# W511A.net
KiCad netlist of a schematic drawn in EAGLE
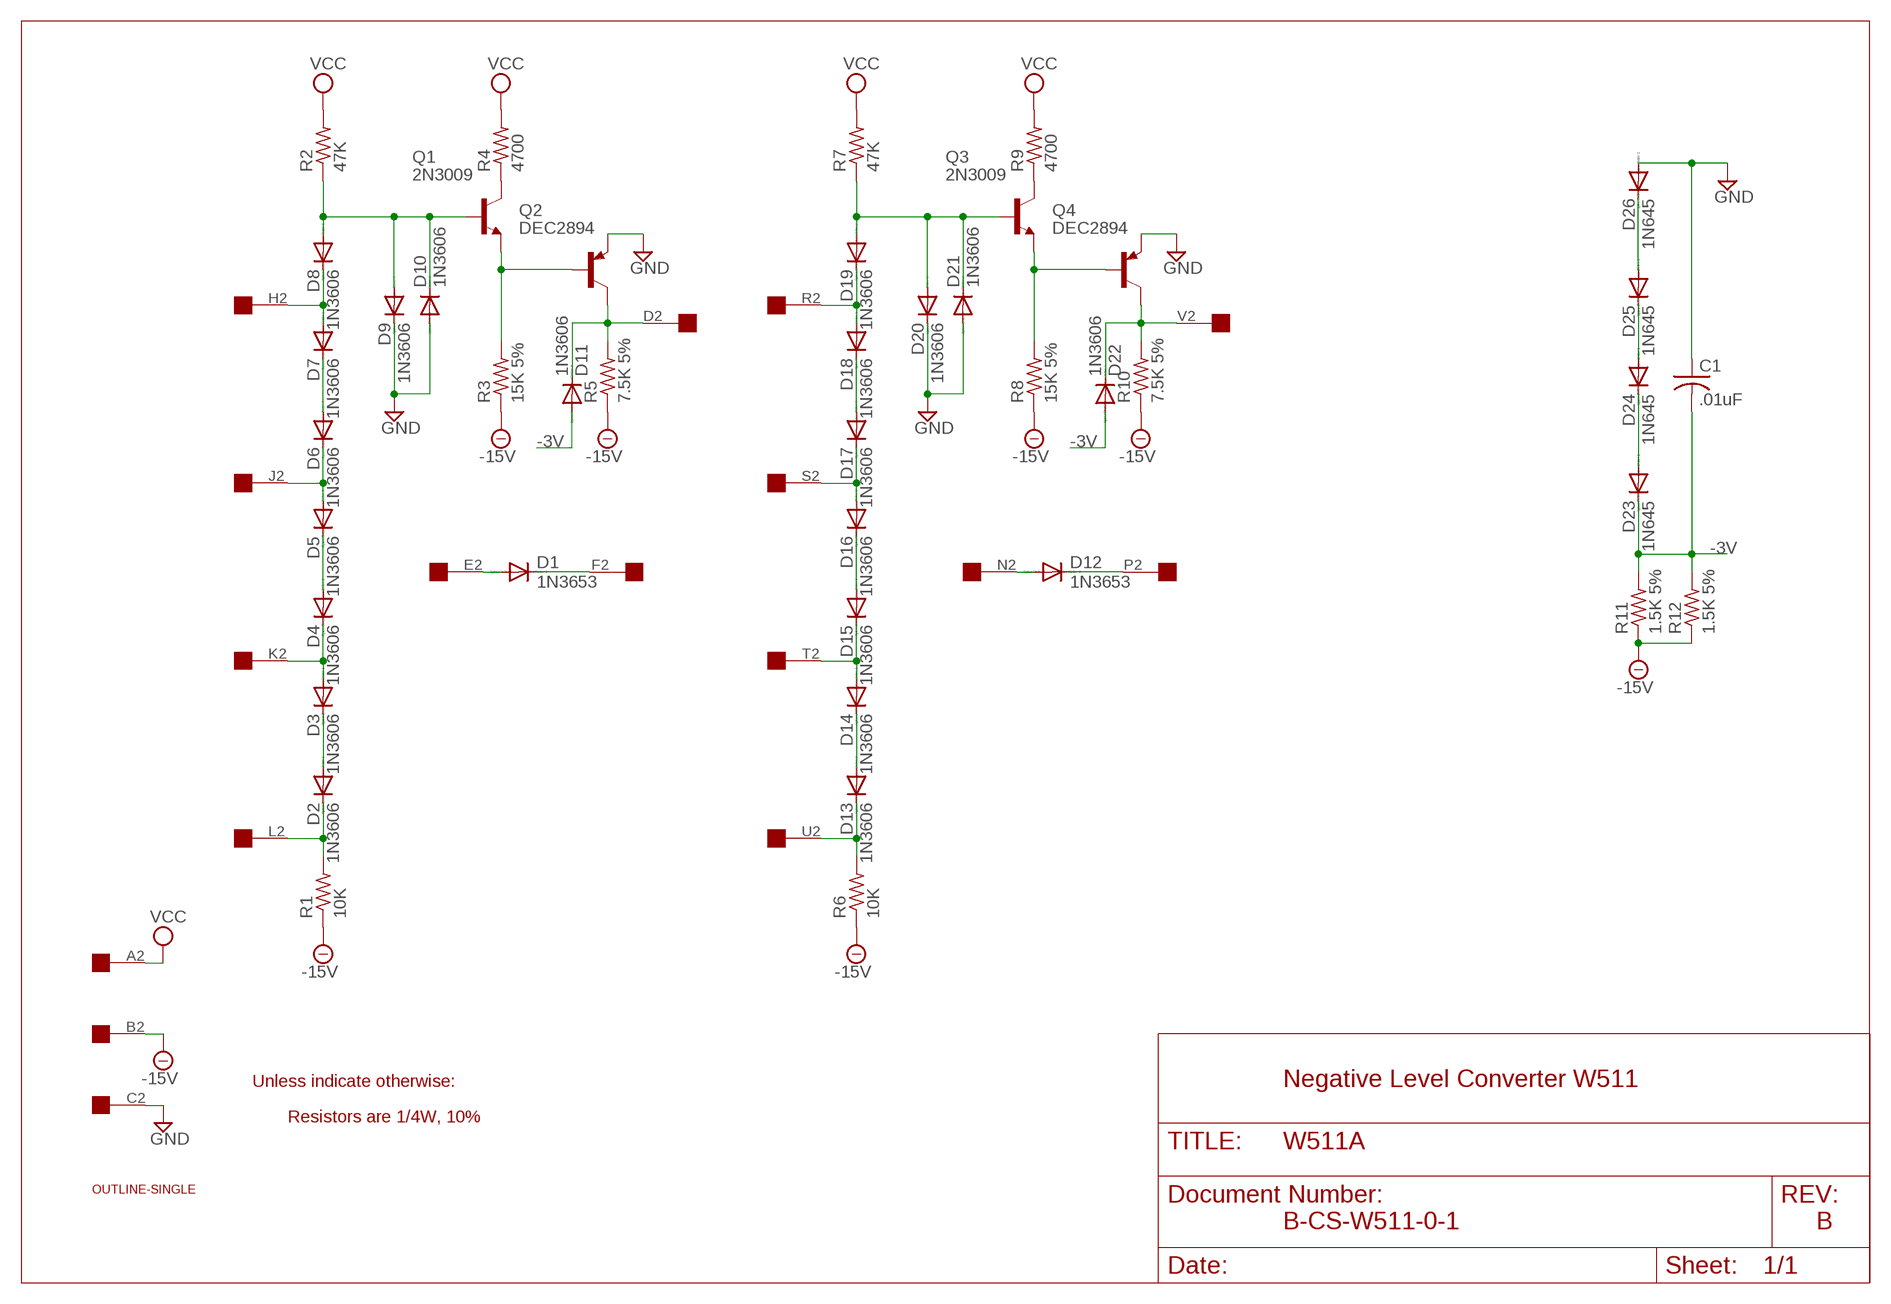
[diagram p0: schematic, sheet 1]

(export (version "E")
  (design (tool "Eeschema 10.0.6"))
  (components
    (comp (ref "C1")
      (value ".01uF")
      (footprint "eagle-import:C050-025X075")
      (libsource (lib "eagle-import") (part "C-US050-025X075"))
    )
    (comp (ref "D1")
      (value "1N3653")
      (footprint "eagle-import:DO35-10")
      (libsource (lib "eagle-import") (part "1N4148DO35-10"))
    )
    (comp (ref "D2")
      (value "1N3606")
      (footprint "eagle-import:DO35-10")
      (libsource (lib "eagle-import") (part "1N4148DO35-10"))
    )
    (comp (ref "D3")
      (value "1N3606")
      (footprint "eagle-import:DO35-10")
      (libsource (lib "eagle-import") (part "1N4148DO35-10"))
    )
    (comp (ref "D4")
      (value "1N3606")
      (footprint "eagle-import:DO35-10")
      (libsource (lib "eagle-import") (part "1N4148DO35-10"))
    )
    (comp (ref "D5")
      (value "1N3606")
      (footprint "eagle-import:DO35-10")
      (libsource (lib "eagle-import") (part "1N4148DO35-10"))
    )
    (comp (ref "D6")
      (value "1N3606")
      (footprint "eagle-import:DO35-10")
      (libsource (lib "eagle-import") (part "1N4148DO35-10"))
    )
    (comp (ref "D7")
      (value "1N3606")
      (footprint "eagle-import:DO35-10")
      (libsource (lib "eagle-import") (part "1N4148DO35-10"))
    )
    (comp (ref "D8")
      (value "1N3606")
      (footprint "eagle-import:DO35-10")
      (libsource (lib "eagle-import") (part "1N4148DO35-10"))
    )
    (comp (ref "D9")
      (value "1N3606")
      (footprint "eagle-import:DO35-10")
      (libsource (lib "eagle-import") (part "1N4148DO35-10"))
    )
    (comp (ref "D10")
      (value "1N3606")
      (footprint "eagle-import:DO35-10")
      (libsource (lib "eagle-import") (part "1N4148DO35-10"))
    )
    (comp (ref "D11")
      (value "1N3606")
      (footprint "eagle-import:DO35-10")
      (libsource (lib "eagle-import") (part "1N4148DO35-10"))
    )
    (comp (ref "D12")
      (value "1N3653")
      (footprint "eagle-import:DO35-10")
      (libsource (lib "eagle-import") (part "1N4148DO35-10"))
    )
    (comp (ref "D13")
      (value "1N3606")
      (footprint "eagle-import:DO35-10")
      (libsource (lib "eagle-import") (part "1N4148DO35-10"))
    )
    (comp (ref "D14")
      (value "1N3606")
      (footprint "eagle-import:DO35-10")
      (libsource (lib "eagle-import") (part "1N4148DO35-10"))
    )
    (comp (ref "D15")
      (value "1N3606")
      (footprint "eagle-import:DO35-10")
      (libsource (lib "eagle-import") (part "1N4148DO35-10"))
    )
    (comp (ref "D16")
      (value "1N3606")
      (footprint "eagle-import:DO35-10")
      (libsource (lib "eagle-import") (part "1N4148DO35-10"))
    )
    (comp (ref "D17")
      (value "1N3606")
      (footprint "eagle-import:DO35-10")
      (libsource (lib "eagle-import") (part "1N4148DO35-10"))
    )
    (comp (ref "D18")
      (value "1N3606")
      (footprint "eagle-import:DO35-10")
      (libsource (lib "eagle-import") (part "1N4148DO35-10"))
    )
    (comp (ref "D19")
      (value "1N3606")
      (footprint "eagle-import:DO35-10")
      (libsource (lib "eagle-import") (part "1N4148DO35-10"))
    )
    (comp (ref "D20")
      (value "1N3606")
      (footprint "eagle-import:DO35-10")
      (libsource (lib "eagle-import") (part "1N4148DO35-10"))
    )
    (comp (ref "D21")
      (value "1N3606")
      (footprint "eagle-import:DO35-10")
      (libsource (lib "eagle-import") (part "1N4148DO35-10"))
    )
    (comp (ref "D22")
      (value "1N3606")
      (footprint "eagle-import:DO35-10")
      (libsource (lib "eagle-import") (part "1N4148DO35-10"))
    )
    (comp (ref "D23")
      (value "1N645")
      (footprint "eagle-import:DO35-10")
      (libsource (lib "eagle-import") (part "1N4148DO35-10"))
    )
    (comp (ref "D24")
      (value "1N645")
      (footprint "eagle-import:DO35-10")
      (libsource (lib "eagle-import") (part "1N4148DO35-10"))
    )
    (comp (ref "D25")
      (value "1N645")
      (footprint "eagle-import:DO35-10")
      (libsource (lib "eagle-import") (part "1N4148DO35-10"))
    )
    (comp (ref "D26")
      (value "1N645")
      (footprint "eagle-import:DO35-10")
      (libsource (lib "eagle-import") (part "1N4148DO35-10"))
    )
    (comp (ref "EDGE")
      (value "EDGE-1")
      (footprint "eagle-import:EDGE-CON1")
      (libsource (lib "eagle-import") (part "EDGE-1"))
    )
    (comp (ref "Q1")
      (value "2N3009")
      (footprint "eagle-import:TO5")
      (libsource (lib "eagle-import") (part "2N2102"))
    )
    (comp (ref "Q2")
      (value "DEC2894")
      (footprint "eagle-import:TO39")
      (libsource (lib "eagle-import") (part "2N2904"))
    )
    (comp (ref "Q3")
      (value "2N3009")
      (footprint "eagle-import:TO5")
      (libsource (lib "eagle-import") (part "2N2102"))
    )
    (comp (ref "Q4")
      (value "DEC2894")
      (footprint "eagle-import:TO39")
      (libsource (lib "eagle-import") (part "2N2904"))
    )
    (comp (ref "R1")
      (value "10K")
      (footprint "eagle-import:0207_10")
      (libsource (lib "eagle-import") (part "R-US_0207/10"))
    )
    (comp (ref "R2")
      (value "47K")
      (footprint "eagle-import:0207_10")
      (libsource (lib "eagle-import") (part "R-US_0207/10"))
    )
    (comp (ref "R3")
      (value "15K 5%")
      (footprint "eagle-import:0207_10")
      (libsource (lib "eagle-import") (part "R-US_0207/10"))
    )
    (comp (ref "R4")
      (value "4700")
      (footprint "eagle-import:0207_10")
      (libsource (lib "eagle-import") (part "R-US_0207/10"))
    )
    (comp (ref "R5")
      (value "7.5K 5%")
      (footprint "eagle-import:0207_10")
      (libsource (lib "eagle-import") (part "R-US_0207/10"))
    )
    (comp (ref "R6")
      (value "10K")
      (footprint "eagle-import:0207_10")
      (libsource (lib "eagle-import") (part "R-US_0207/10"))
    )
    (comp (ref "R7")
      (value "47K")
      (footprint "eagle-import:0207_10")
      (libsource (lib "eagle-import") (part "R-US_0207/10"))
    )
    (comp (ref "R8")
      (value "15K 5%")
      (footprint "eagle-import:0207_10")
      (libsource (lib "eagle-import") (part "R-US_0207/10"))
    )
    (comp (ref "R9")
      (value "4700")
      (footprint "eagle-import:0207_10")
      (libsource (lib "eagle-import") (part "R-US_0207/10"))
    )
    (comp (ref "R10")
      (value "7.5K 5%")
      (footprint "eagle-import:0207_10")
      (libsource (lib "eagle-import") (part "R-US_0207/10"))
    )
    (comp (ref "R11")
      (value "1.5K 5%")
      (footprint "eagle-import:0207_10")
      (libsource (lib "eagle-import") (part "R-US_0207/10"))
    )
    (comp (ref "R12")
      (value "1.5K 5%")
      (footprint "eagle-import:0207_10")
      (libsource (lib "eagle-import") (part "R-US_0207/10"))
    )
    (comp (ref "U$1")
      (value "OUTLINE-SINGLE")
      (footprint "eagle-import:SINGLE")
      (libsource (lib "eagle-import") (part "OUTLINE-SINGLE"))
    )
  )
  (nets
    (net (code "1") (name "-15V") (class "Default")
      (node (ref "EDGE") (pin "B2") (pinfunction "1_B2") (pintype "bidirectional"))
      (node (ref "R1") (pin "1") (pinfunction "1_1") (pintype "passive"))
      (node (ref "R10") (pin "1") (pinfunction "1_1") (pintype "passive"))
      (node (ref "R11") (pin "1") (pinfunction "1_1") (pintype "passive"))
      (node (ref "R12") (pin "1") (pinfunction "1_1") (pintype "passive"))
      (node (ref "R3") (pin "1") (pinfunction "1_1") (pintype "passive"))
      (node (ref "R5") (pin "1") (pinfunction "1_1") (pintype "passive"))
      (node (ref "R6") (pin "1") (pinfunction "1_1") (pintype "passive"))
      (node (ref "R8") (pin "1") (pinfunction "1_1") (pintype "passive"))
    )
    (net (code "2") (name "/-3V") (class "Default")
      (node (ref "C1") (pin "2") (pinfunction "2_2") (pintype "passive"))
      (node (ref "D11") (pin "A") (pinfunction "A_A") (pintype "passive"))
      (node (ref "D22") (pin "A") (pinfunction "A_A") (pintype "passive"))
      (node (ref "D23") (pin "C") (pinfunction "C_C") (pintype "passive"))
      (node (ref "R11") (pin "2") (pinfunction "2_2") (pintype "passive"))
      (node (ref "R12") (pin "2") (pinfunction "2_2") (pintype "passive"))
    )
    (net (code "3") (name "GND") (class "Default")
      (node (ref "C1") (pin "1") (pinfunction "1_1") (pintype "passive"))
      (node (ref "D10") (pin "A") (pinfunction "A_A") (pintype "passive"))
      (node (ref "D20") (pin "C") (pinfunction "C_C") (pintype "passive"))
      (node (ref "D21") (pin "A") (pinfunction "A_A") (pintype "passive"))
      (node (ref "D26") (pin "A") (pinfunction "A_A") (pintype "passive"))
      (node (ref "D9") (pin "C") (pinfunction "C_C") (pintype "passive"))
      (node (ref "EDGE") (pin "C2") (pinfunction "1_C2") (pintype "bidirectional"))
      (node (ref "Q2") (pin "1") (pinfunction "E_1") (pintype "passive"))
      (node (ref "Q4") (pin "1") (pinfunction "E_1") (pintype "passive"))
    )
    (net (code "4") (name "Net-(D2-PadA)") (class "Default")
      (node (ref "D2") (pin "A") (pinfunction "A_A") (pintype "passive"))
      (node (ref "D3") (pin "C") (pinfunction "C_C") (pintype "passive"))
    )
    (net (code "5") (name "Net-(D4-PadA)") (class "Default")
      (node (ref "D4") (pin "A") (pinfunction "A_A") (pintype "passive"))
      (node (ref "D5") (pin "C") (pinfunction "C_C") (pintype "passive"))
    )
    (net (code "6") (name "Net-(D6-PadA)") (class "Default")
      (node (ref "D6") (pin "A") (pinfunction "A_A") (pintype "passive"))
      (node (ref "D7") (pin "C") (pinfunction "C_C") (pintype "passive"))
    )
    (net (code "7") (name "Net-(D13-PadA)") (class "Default")
      (node (ref "D13") (pin "A") (pinfunction "A_A") (pintype "passive"))
      (node (ref "D14") (pin "C") (pinfunction "C_C") (pintype "passive"))
    )
    (net (code "8") (name "Net-(D15-PadA)") (class "Default")
      (node (ref "D15") (pin "A") (pinfunction "A_A") (pintype "passive"))
      (node (ref "D16") (pin "C") (pinfunction "C_C") (pintype "passive"))
    )
    (net (code "9") (name "Net-(D17-PadA)") (class "Default")
      (node (ref "D17") (pin "A") (pinfunction "A_A") (pintype "passive"))
      (node (ref "D18") (pin "C") (pinfunction "C_C") (pintype "passive"))
    )
    (net (code "10") (name "Net-(D23-PadA)") (class "Default")
      (node (ref "D23") (pin "A") (pinfunction "A_A") (pintype "passive"))
      (node (ref "D24") (pin "C") (pinfunction "C_C") (pintype "passive"))
    )
    (net (code "11") (name "Net-(D24-PadA)") (class "Default")
      (node (ref "D24") (pin "A") (pinfunction "A_A") (pintype "passive"))
      (node (ref "D25") (pin "C") (pinfunction "C_C") (pintype "passive"))
    )
    (net (code "12") (name "Net-(D25-PadA)") (class "Default")
      (node (ref "D25") (pin "A") (pinfunction "A_A") (pintype "passive"))
      (node (ref "D26") (pin "C") (pinfunction "C_C") (pintype "passive"))
    )
    (net (code "13") (name "Net-(EDGED-1)") (class "Default")
      (node (ref "D11") (pin "C") (pinfunction "C_C") (pintype "passive"))
      (node (ref "EDGE") (pin "D2") (pinfunction "1_D2") (pintype "bidirectional"))
      (node (ref "Q2") (pin "3") (pinfunction "C_3") (pintype "passive"))
      (node (ref "R5") (pin "2") (pinfunction "2_2") (pintype "passive"))
    )
    (net (code "14") (name "Net-(EDGEE-1)") (class "Default")
      (node (ref "D1") (pin "A") (pinfunction "A_A") (pintype "passive"))
      (node (ref "EDGE") (pin "E2") (pinfunction "1_E2") (pintype "bidirectional"))
    )
    (net (code "15") (name "Net-(EDGEF-1)") (class "Default")
      (node (ref "D1") (pin "C") (pinfunction "C_C") (pintype "passive"))
      (node (ref "EDGE") (pin "F2") (pinfunction "1_F2") (pintype "bidirectional"))
    )
    (net (code "16") (name "Net-(EDGEG-1)") (class "Default")
      (node (ref "D7") (pin "A") (pinfunction "A_A") (pintype "passive"))
      (node (ref "D8") (pin "C") (pinfunction "C_C") (pintype "passive"))
      (node (ref "EDGE") (pin "H2") (pinfunction "1_H2") (pintype "bidirectional"))
    )
    (net (code "17") (name "Net-(EDGEH-1)") (class "Default")
      (node (ref "D5") (pin "A") (pinfunction "A_A") (pintype "passive"))
      (node (ref "D6") (pin "C") (pinfunction "C_C") (pintype "passive"))
      (node (ref "EDGE") (pin "J2") (pinfunction "1_J2") (pintype "bidirectional"))
    )
    (net (code "18") (name "Net-(EDGEI-1)") (class "Default")
      (node (ref "D3") (pin "A") (pinfunction "A_A") (pintype "passive"))
      (node (ref "D4") (pin "C") (pinfunction "C_C") (pintype "passive"))
      (node (ref "EDGE") (pin "K2") (pinfunction "1_K2") (pintype "bidirectional"))
    )
    (net (code "19") (name "Net-(EDGEJ-1)") (class "Default")
      (node (ref "D2") (pin "C") (pinfunction "C_C") (pintype "passive"))
      (node (ref "EDGE") (pin "L2") (pinfunction "1_L2") (pintype "bidirectional"))
      (node (ref "R1") (pin "2") (pinfunction "2_2") (pintype "passive"))
    )
    (net (code "20") (name "Net-(EDGEL-1)") (class "Default")
      (node (ref "D12") (pin "A") (pinfunction "A_A") (pintype "passive"))
      (node (ref "EDGE") (pin "N2") (pinfunction "1_N2") (pintype "bidirectional"))
    )
    (net (code "21") (name "Net-(EDGEM-1)") (class "Default")
      (node (ref "D12") (pin "C") (pinfunction "C_C") (pintype "passive"))
      (node (ref "EDGE") (pin "P2") (pinfunction "1_P2") (pintype "bidirectional"))
    )
    (net (code "22") (name "Net-(EDGEN-1)") (class "Default")
      (node (ref "D18") (pin "A") (pinfunction "A_A") (pintype "passive"))
      (node (ref "D19") (pin "C") (pinfunction "C_C") (pintype "passive"))
      (node (ref "EDGE") (pin "R2") (pinfunction "1_R2") (pintype "bidirectional"))
    )
    (net (code "23") (name "Net-(EDGEO-1)") (class "Default")
      (node (ref "D16") (pin "A") (pinfunction "A_A") (pintype "passive"))
      (node (ref "D17") (pin "C") (pinfunction "C_C") (pintype "passive"))
      (node (ref "EDGE") (pin "S2") (pinfunction "1_S2") (pintype "bidirectional"))
    )
    (net (code "24") (name "Net-(EDGEP-1)") (class "Default")
      (node (ref "D14") (pin "A") (pinfunction "A_A") (pintype "passive"))
      (node (ref "D15") (pin "C") (pinfunction "C_C") (pintype "passive"))
      (node (ref "EDGE") (pin "T2") (pinfunction "1_T2") (pintype "bidirectional"))
    )
    (net (code "25") (name "Net-(EDGEQ-1)") (class "Default")
      (node (ref "D13") (pin "C") (pinfunction "C_C") (pintype "passive"))
      (node (ref "EDGE") (pin "U2") (pinfunction "1_U2") (pintype "bidirectional"))
      (node (ref "R6") (pin "2") (pinfunction "2_2") (pintype "passive"))
    )
    (net (code "26") (name "Net-(EDGER-1)") (class "Default")
      (node (ref "D22") (pin "C") (pinfunction "C_C") (pintype "passive"))
      (node (ref "EDGE") (pin "V2") (pinfunction "1_V2") (pintype "bidirectional"))
      (node (ref "Q4") (pin "3") (pinfunction "C_3") (pintype "passive"))
      (node (ref "R10") (pin "2") (pinfunction "2_2") (pintype "passive"))
    )
    (net (code "27") (name "Net-(Q1-B)") (class "Default")
      (node (ref "D10") (pin "C") (pinfunction "C_C") (pintype "passive"))
      (node (ref "D8") (pin "A") (pinfunction "A_A") (pintype "passive"))
      (node (ref "D9") (pin "A") (pinfunction "A_A") (pintype "passive"))
      (node (ref "Q1") (pin "2") (pinfunction "B_2") (pintype "passive"))
      (node (ref "R2") (pin "1") (pinfunction "1_1") (pintype "passive"))
    )
    (net (code "28") (name "Net-(Q1-C)") (class "Default")
      (node (ref "Q1") (pin "3") (pinfunction "C_3") (pintype "passive"))
      (node (ref "R4") (pin "1") (pinfunction "1_1") (pintype "passive"))
    )
    (net (code "29") (name "Net-(Q1-E)") (class "Default")
      (node (ref "Q1") (pin "1") (pinfunction "E_1") (pintype "passive"))
      (node (ref "Q2") (pin "2") (pinfunction "B_2") (pintype "passive"))
      (node (ref "R3") (pin "2") (pinfunction "2_2") (pintype "passive"))
    )
    (net (code "30") (name "Net-(Q3-B)") (class "Default")
      (node (ref "D19") (pin "A") (pinfunction "A_A") (pintype "passive"))
      (node (ref "D20") (pin "A") (pinfunction "A_A") (pintype "passive"))
      (node (ref "D21") (pin "C") (pinfunction "C_C") (pintype "passive"))
      (node (ref "Q3") (pin "2") (pinfunction "B_2") (pintype "passive"))
      (node (ref "R7") (pin "1") (pinfunction "1_1") (pintype "passive"))
    )
    (net (code "31") (name "Net-(Q3-C)") (class "Default")
      (node (ref "Q3") (pin "3") (pinfunction "C_3") (pintype "passive"))
      (node (ref "R9") (pin "1") (pinfunction "1_1") (pintype "passive"))
    )
    (net (code "32") (name "Net-(Q3-E)") (class "Default")
      (node (ref "Q3") (pin "1") (pinfunction "E_1") (pintype "passive"))
      (node (ref "Q4") (pin "2") (pinfunction "B_2") (pintype "passive"))
      (node (ref "R8") (pin "2") (pinfunction "2_2") (pintype "passive"))
    )
    (net (code "33") (name "VCC") (class "Default")
      (node (ref "EDGE") (pin "A2") (pinfunction "1_A2") (pintype "bidirectional"))
      (node (ref "R2") (pin "2") (pinfunction "2_2") (pintype "passive"))
      (node (ref "R4") (pin "2") (pinfunction "2_2") (pintype "passive"))
      (node (ref "R7") (pin "2") (pinfunction "2_2") (pintype "passive"))
      (node (ref "R9") (pin "2") (pinfunction "2_2") (pintype "passive"))
    )
  )
)
